# RPI_3.net
KiCad netlist of a schematic drawn in Altium Designer
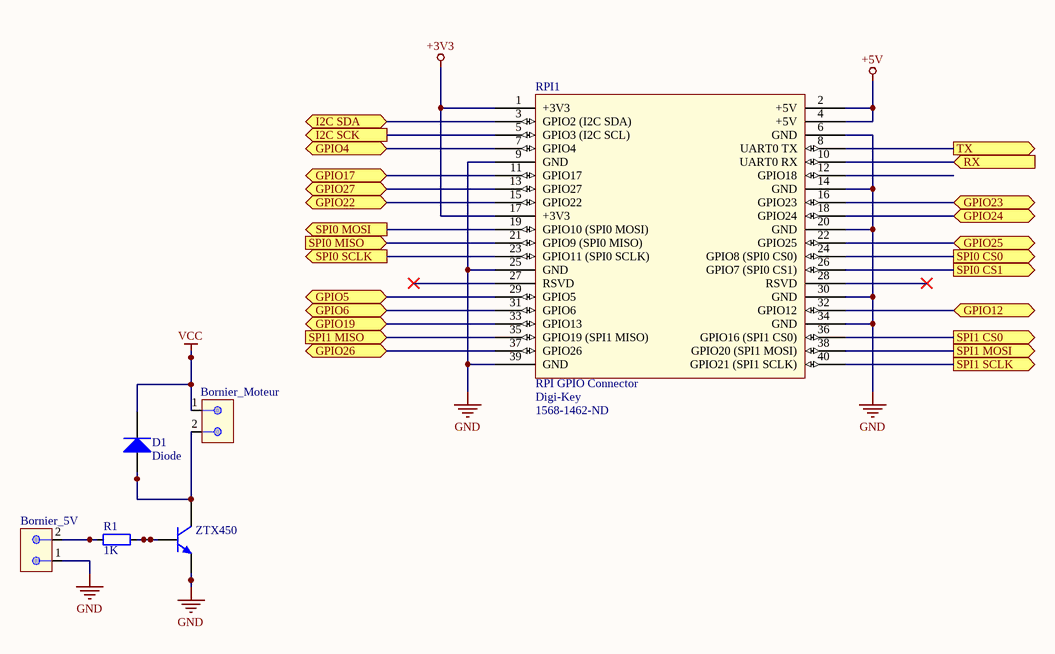
[diagram p0: RPI 3.SchDoc]

(export (version "E")
  (design (tool "Eeschema 10.0.6"))
  (components
    (comp (ref "Bornier_5V") (value "~") (footprint "Bornier2") (libsource (lib "") (part "Bornier2_1")))
    (comp (ref "Bornier_Moteur")
      (value "~")
      (footprint "Bornier2")
      (libsource (lib "iut_lib_extras") (part "Bornier2"))
    )
    (comp (ref "D1")
      (value "Diode")
      (footprint "DIODE_iut")
      (description "Default Diode")
      (fields
        (field (name "MANUFACTURER") "Generic Components")
        (field (name "PUBLISHER") "Altium Hobart Technology Centre")
      )
      (libsource (lib "iut_lib_1004") (part "Diode"))
    )
    (comp (ref "R1")
      (value "1K")
      (footprint "AXIAL-0.4_IUT")
      (description "Resistor")
      (fields
        (field (name "MANUFACTURER") "Generic Components")
        (field (name "Comment") "Res2")
        (field (name "PUBLISHER") "Altium Hobart Technology Centre")
      )
      (libsource (lib "iut_lib_1004") (part "Res2"))
    )
    (comp (ref "RPI1")
      (value "RPI GPIO Connector")
      (footprint "rpi")
      (description "GPIO Header for Raspberry Pi A+/B+/Pi 2/Pi 3 - 2x20")
      (fields
        (field (name "MANUFACTURER") "SparkFun Electronics")
        (field (name "MANUFACTURER PART NUMBER") "PRT-14017")
        (field (name "SUPPLIER 1") "Digi-Key")
        (field (name "SUPPLIER PART NUMBER 1") "1568-1462-ND")
      )
      (libsource (lib "rpi") (part "rpi connector"))
    )
    (comp (ref "ZTX450") (value "~") (footprint "TO_92") (libsource (lib "iut_lib_extras") (part "BC547")))
  )
  (nets
    (net (code "1") (name "+3V3") (class "Default")
      (node (ref "RPI1") (pin "1") (pinfunction "+3V3_1") (pintype "power_in"))
      (node (ref "RPI1") (pin "17") (pinfunction "+3V3_17") (pintype "power_in"))
    )
    (net (code "2") (name "+5V") (class "Default")
      (node (ref "RPI1") (pin "2") (pinfunction "+5V_2") (pintype "power_in"))
      (node (ref "RPI1") (pin "4") (pinfunction "+5V_4") (pintype "power_in"))
    )
    (net (code "3") (name "/GPIO4") (class "Default")
      (node (ref "RPI1") (pin "7") (pinfunction "GPIO4_7") (pintype "bidirectional"))
    )
    (net (code "4") (name "/GPIO5") (class "Default")
      (node (ref "RPI1") (pin "29") (pinfunction "GPIO5_29") (pintype "bidirectional"))
    )
    (net (code "5") (name "/GPIO6") (class "Default")
      (node (ref "RPI1") (pin "31") (pinfunction "GPIO6_31") (pintype "bidirectional"))
    )
    (net (code "6") (name "/GPIO12") (class "Default")
      (node (ref "RPI1") (pin "32") (pinfunction "GPIO12_32") (pintype "bidirectional"))
    )
    (net (code "7") (name "/GPIO17") (class "Default")
      (node (ref "RPI1") (pin "11") (pinfunction "GPIO17_11") (pintype "bidirectional"))
    )
    (net (code "8") (name "/GPIO19") (class "Default")
      (node (ref "RPI1") (pin "33") (pinfunction "GPIO13_33") (pintype "bidirectional"))
    )
    (net (code "9") (name "/GPIO22") (class "Default")
      (node (ref "RPI1") (pin "15") (pinfunction "GPIO22_15") (pintype "bidirectional"))
    )
    (net (code "10") (name "/GPIO23") (class "Default")
      (node (ref "RPI1") (pin "16") (pinfunction "GPIO23_16") (pintype "bidirectional"))
    )
    (net (code "11") (name "/GPIO24") (class "Default")
      (node (ref "RPI1") (pin "18") (pinfunction "GPIO24_18") (pintype "bidirectional"))
    )
    (net (code "12") (name "/GPIO25") (class "Default")
      (node (ref "RPI1") (pin "22") (pinfunction "GPIO25_22") (pintype "bidirectional"))
    )
    (net (code "13") (name "/GPIO26") (class "Default")
      (node (ref "RPI1") (pin "37") (pinfunction "GPIO26_37") (pintype "bidirectional"))
    )
    (net (code "14") (name "/GPIO27") (class "Default")
      (node (ref "RPI1") (pin "13") (pinfunction "GPIO27_13") (pintype "bidirectional"))
    )
    (net (code "15") (name "/I2C SCK") (class "Default")
      (node (ref "RPI1") (pin "5") (pinfunction "GPIO3_(I2C_SCL)_5") (pintype "bidirectional"))
    )
    (net (code "16") (name "/I2C SDA") (class "Default")
      (node (ref "RPI1") (pin "3") (pinfunction "GPIO2_(I2C_SDA)_3") (pintype "bidirectional"))
    )
    (net (code "17") (name "/RX") (class "Default")
      (node (ref "RPI1") (pin "10") (pinfunction "UART0_RX_10") (pintype "bidirectional"))
    )
    (net (code "18") (name "/SPI0 CS0") (class "Default")
      (node (ref "RPI1") (pin "24") (pinfunction "GPIO8_(SPI0_CS0)_24") (pintype "bidirectional"))
    )
    (net (code "19") (name "/SPI0 CS1") (class "Default")
      (node (ref "RPI1") (pin "26") (pinfunction "GPIO7_(SPI0_CS1)_26") (pintype "bidirectional"))
    )
    (net (code "20") (name "/SPI0 MISO") (class "Default")
      (node (ref "RPI1") (pin "21") (pinfunction "GPIO9_(SPI0_MISO)_21") (pintype "bidirectional"))
    )
    (net (code "21") (name "/SPI0 MOSI") (class "Default")
      (node (ref "RPI1") (pin "19") (pinfunction "GPIO10_(SPI0_MOSI)_19") (pintype "bidirectional"))
    )
    (net (code "22") (name "/SPI0 SCLK") (class "Default")
      (node (ref "RPI1") (pin "23") (pinfunction "GPIO11_(SPI0_SCLK)_23") (pintype "bidirectional"))
    )
    (net (code "23") (name "/SPI1 CS0") (class "Default")
      (node (ref "RPI1") (pin "36") (pinfunction "GPIO16_(SPI1_CS0)_36") (pintype "bidirectional"))
    )
    (net (code "24") (name "/SPI1 MISO") (class "Default")
      (node (ref "RPI1") (pin "35") (pinfunction "GPIO19_(SPI1_MISO)_35") (pintype "bidirectional"))
    )
    (net (code "25") (name "/SPI1 MOSI") (class "Default")
      (node (ref "RPI1") (pin "38") (pinfunction "GPIO20_(SPI1_MOSI)_38") (pintype "bidirectional"))
    )
    (net (code "26") (name "/SPI1 SCLK") (class "Default")
      (node (ref "RPI1") (pin "40") (pinfunction "GPIO21_(SPI1_SCLK)_40") (pintype "bidirectional"))
    )
    (net (code "27") (name "/TX") (class "Default")
      (node (ref "RPI1") (pin "8") (pinfunction "UART0_TX_8") (pintype "bidirectional"))
    )
    (net (code "28") (name "GND") (class "Default")
      (node (ref "Bornier_5V") (pin "1") (pinfunction "1_1") (pintype "passive"))
      (node (ref "RPI1") (pin "14") (pinfunction "GND_14") (pintype "power_in"))
      (node (ref "RPI1") (pin "20") (pinfunction "GND_20") (pintype "power_in"))
      (node (ref "RPI1") (pin "25") (pinfunction "GND_25") (pintype "power_in"))
      (node (ref "RPI1") (pin "30") (pinfunction "GND_30") (pintype "power_in"))
      (node (ref "RPI1") (pin "34") (pinfunction "GND_34") (pintype "passive"))
      (node (ref "RPI1") (pin "39") (pinfunction "GND_39") (pintype "power_in"))
      (node (ref "RPI1") (pin "6") (pinfunction "GND_6") (pintype "power_in"))
      (node (ref "RPI1") (pin "9") (pinfunction "GND_9") (pintype "power_in"))
      (node (ref "ZTX450") (pin "1") (pinfunction "E_1") (pintype "passive"))
    )
    (net (code "29") (name "Net-(Bornier_5V-Pad2)") (class "Default")
      (node (ref "Bornier_5V") (pin "2") (pinfunction "2_2") (pintype "passive"))
      (node (ref "R1") (pin "1") (pinfunction "1_1") (pintype "passive"))
    )
    (net (code "30") (name "Net-(D1-A)") (class "Default")
      (node (ref "Bornier_Moteur") (pin "2") (pinfunction "2_2") (pintype "passive"))
      (node (ref "D1") (pin "1") (pinfunction "A_1") (pintype "passive"))
      (node (ref "ZTX450") (pin "3") (pinfunction "C_3") (pintype "passive"))
    )
    (net (code "31") (name "Net-(ZTX450-B)") (class "Default")
      (node (ref "R1") (pin "2") (pinfunction "2_2") (pintype "passive"))
      (node (ref "ZTX450") (pin "2") (pinfunction "B_2") (pintype "passive"))
    )
    (net (code "32") (name "VCC") (class "Default")
      (node (ref "Bornier_Moteur") (pin "1") (pinfunction "1_1") (pintype "passive"))
      (node (ref "D1") (pin "2") (pinfunction "K_2") (pintype "passive"))
    )
    (net (code "33") (name "unconnected-(RPI1-GPIO18-Pad12)") (class "Default")
      (node (ref "RPI1") (pin "12") (pinfunction "GPIO18_12") (pintype "bidirectional"))
    )
    (net (code "34") (name "unconnected-(RPI1-RSVD-Pad27)") (class "Default")
      (node (ref "RPI1") (pin "27") (pinfunction "RSVD_27") (pintype "passive+no_connect"))
    )
    (net (code "35") (name "unconnected-(RPI1-RSVD-Pad28)") (class "Default")
      (node (ref "RPI1") (pin "28") (pinfunction "RSVD_28") (pintype "passive+no_connect"))
    )
  )
)
